# 5V-to-12V-Converter.net
KiCad netlist of a schematic drawn in EAGLE
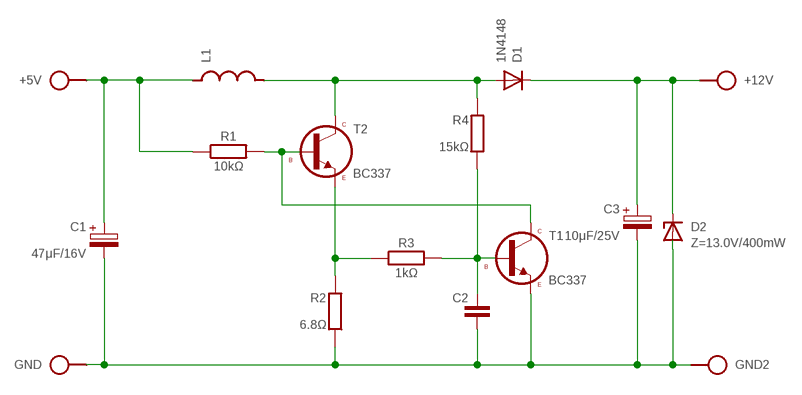
[diagram p0: schematic, sheet 1]

(export (version "E")
  (design (tool "Eeschema 10.0.6"))
  (components
    (comp (ref "+5V")
      (value "SPAD")
      (footprint "eagle-import:SPAD")
      (libsource (lib "eagle-import") (part "SPAD"))
    )
    (comp (ref "+12V")
      (value "SPAD")
      (footprint "eagle-import:SPAD")
      (libsource (lib "eagle-import") (part "SPAD"))
    )
    (comp (ref "C1")
      (value "47μF/16V")
      (footprint "eagle-import:E2.5-4_V")
      (libsource (lib "eagle-import") (part "CPOLE2,5-4/V"))
    )
    (comp (ref "C2")
      (value "C050-025X075")
      (footprint "eagle-import:C050-025X075")
      (libsource (lib "eagle-import") (part "C050-025X075"))
    )
    (comp (ref "C3")
      (value "10μF/25V")
      (footprint "eagle-import:E2.5-4_V")
      (libsource (lib "eagle-import") (part "CPOLE2,5-4/V"))
    )
    (comp (ref "D1")
      (value "1N4148")
      (footprint "eagle-import:DO34-7")
      (libsource (lib "eagle-import") (part "1N414834-7"))
    )
    (comp (ref "D2")
      (value "Z=13.0V/400mW")
      (footprint "eagle-import:DO34Z10V")
      (libsource (lib "eagle-import") (part "Z-DIODE34Z10V"))
    )
    (comp (ref "GND")
      (value "SPAD")
      (footprint "eagle-import:SPAD")
      (libsource (lib "eagle-import") (part "SPAD"))
    )
    (comp (ref "GND2")
      (value "SPAD")
      (footprint "eagle-import:SPAD")
      (libsource (lib "eagle-import") (part "SPAD"))
    )
    (comp (ref "L1")
      (value "L-SHORTED16-X")
      (footprint "eagle-import:ED16-X")
      (libsource (lib "eagle-import") (part "L-SHORTED16-X"))
    )
    (comp (ref "R1")
      (value "10kΩ")
      (footprint "eagle-import:0204_10")
      (libsource (lib "eagle-import") (part "R-H0204/10"))
    )
    (comp (ref "R2")
      (value "6.8Ω")
      (footprint "eagle-import:0204_10")
      (libsource (lib "eagle-import") (part "R0204/10"))
    )
    (comp (ref "R3")
      (value "1kΩ")
      (footprint "eagle-import:0204_10")
      (libsource (lib "eagle-import") (part "R-H0204/10"))
    )
    (comp (ref "R4")
      (value "15kΩ")
      (footprint "eagle-import:0204_10")
      (libsource (lib "eagle-import") (part "R0204/10"))
    )
    (comp (ref "T1")
      (value "BC337")
      (footprint "eagle-import:TO92-CBE")
      (libsource (lib "eagle-import") (part "BC337CBE"))
    )
    (comp (ref "T2")
      (value "BC337")
      (footprint "eagle-import:TO92-CBE")
      (libsource (lib "eagle-import") (part "BC337CBE"))
    )
  )
  (nets
    (net (code "1") (name "Net-(+5V-P$1)") (class "Default")
      (node (ref "+5V") (pin "1") (pinfunction "P$1_1") (pintype "passive"))
      (node (ref "C1") (pin "+") (pinfunction "+_+") (pintype "passive"))
      (node (ref "L1") (pin "2") (pinfunction "2_2") (pintype "passive"))
      (node (ref "R1") (pin "1") (pinfunction "1_1") (pintype "passive"))
    )
    (net (code "2") (name "Net-(+12V-P$1)") (class "Default")
      (node (ref "+12V") (pin "1") (pinfunction "P$1_1") (pintype "passive"))
      (node (ref "C3") (pin "+") (pinfunction "+_+") (pintype "passive"))
      (node (ref "D1") (pin "C") (pinfunction "C_C") (pintype "passive"))
      (node (ref "D2") (pin "C") (pinfunction "C_C") (pintype "passive"))
    )
    (net (code "3") (name "Net-(GND-P$1)") (class "Default")
      (node (ref "C1") (pin "-") (pinfunction "-_-") (pintype "passive"))
      (node (ref "C2") (pin "2") (pinfunction "2_2") (pintype "passive"))
      (node (ref "C3") (pin "-") (pinfunction "-_-") (pintype "passive"))
      (node (ref "D2") (pin "A") (pinfunction "A_A") (pintype "passive"))
      (node (ref "GND") (pin "1") (pinfunction "P$1_1") (pintype "passive"))
      (node (ref "GND2") (pin "1") (pinfunction "P$1_1") (pintype "passive"))
      (node (ref "R2") (pin "1") (pinfunction "2_1") (pintype "passive"))
      (node (ref "T1") (pin "E") (pinfunction "E_E") (pintype "passive"))
    )
    (net (code "4") (name "Net-(R1-Pad2)") (class "Default")
      (node (ref "R1") (pin "2") (pinfunction "2_2") (pintype "passive"))
      (node (ref "T1") (pin "C") (pinfunction "C_C") (pintype "passive"))
      (node (ref "T2") (pin "B") (pinfunction "B_B") (pintype "passive"))
    )
    (net (code "5") (name "Net-(R2-1)") (class "Default")
      (node (ref "R2") (pin "2") (pinfunction "1_2") (pintype "passive"))
      (node (ref "R3") (pin "1") (pinfunction "1_1") (pintype "passive"))
      (node (ref "T2") (pin "E") (pinfunction "E_E") (pintype "passive"))
    )
    (net (code "6") (name "Net-(R4-1)") (class "Default")
      (node (ref "D1") (pin "A") (pinfunction "A_A") (pintype "passive"))
      (node (ref "L1") (pin "1") (pinfunction "1_1") (pintype "passive"))
      (node (ref "R4") (pin "2") (pinfunction "1_2") (pintype "passive"))
      (node (ref "T2") (pin "C") (pinfunction "C_C") (pintype "passive"))
    )
    (net (code "7") (name "Net-(R4-2)") (class "Default")
      (node (ref "C2") (pin "1") (pinfunction "1_1") (pintype "passive"))
      (node (ref "R3") (pin "2") (pinfunction "2_2") (pintype "passive"))
      (node (ref "R4") (pin "1") (pinfunction "2_1") (pintype "passive"))
      (node (ref "T1") (pin "B") (pinfunction "B_B") (pintype "passive"))
    )
  )
)
